# NG2094_Connector_B.net
KiCad netlist of a schematic drawn in Altium Designer
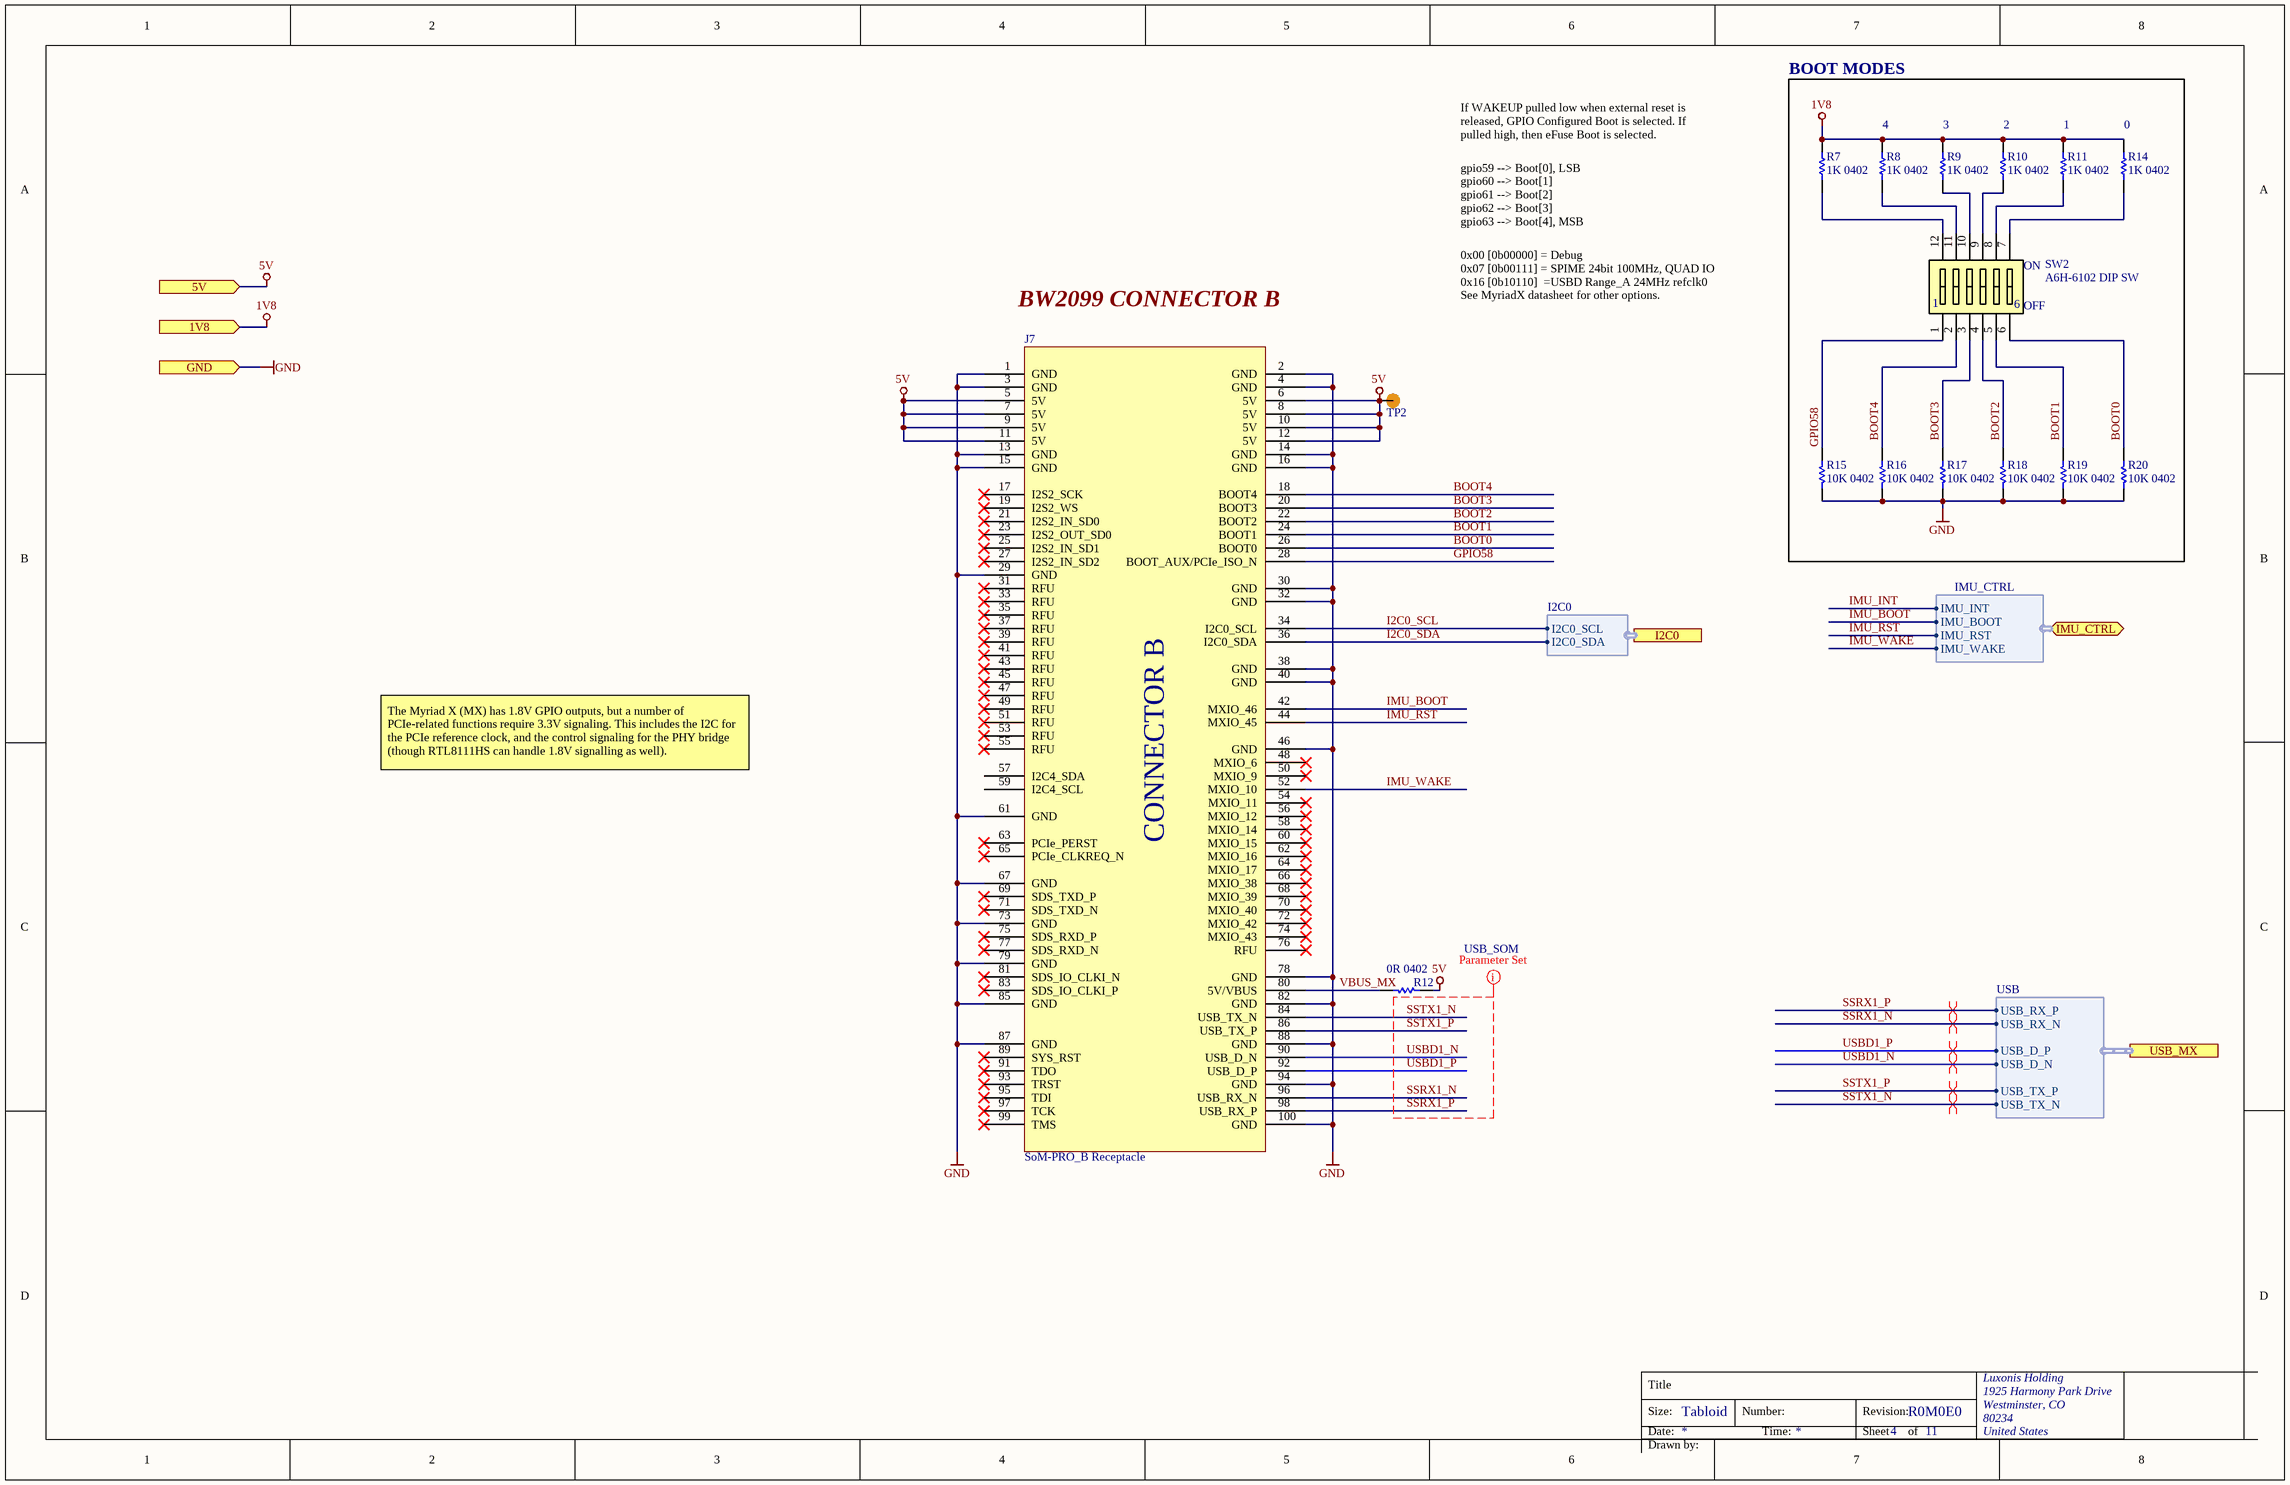
[diagram p0: NG2094_Connector_B.SchDoc]

(export (version "E")
  (design (tool "Eeschema 10.0.6"))
  (components
    (comp (ref "J7")
      (value "SoM-PRO_B Receptacle")
      (footprint "BW2099_SoM:CON_B_BW2099_SoM_DF40HC-3.0-100DS-0.4V_minpad")
      (description "CONN RCPT 100POS 0.4MM SMD GOLD")
      (libsource (lib "BW2099_SoM") (part "DF40HC(3.0)-100DS-0.4V_SoM-PRO_B"))
    )
    (comp (ref "R7")
      (value "1K 0402")
      (footprint "RES_Altium_Vault_Generic:RESC0402(1005)_L")
      (fields (field (name "TOLERANCE") "1%"))
      (libsource (lib "LuxonisMaster") (part "RC0402FR-071KL"))
    )
    (comp (ref "R8")
      (value "1K 0402")
      (footprint "RES_Altium_Vault_Generic:RESC0402(1005)_L")
      (fields (field (name "TOLERANCE") "1%"))
      (libsource (lib "LuxonisMaster") (part "RC0402FR-071KL"))
    )
    (comp (ref "R9")
      (value "1K 0402")
      (footprint "RES_Altium_Vault_Generic:RESC0402(1005)_L")
      (fields (field (name "TOLERANCE") "1%"))
      (libsource (lib "LuxonisMaster") (part "RC0402FR-071KL"))
    )
    (comp (ref "R10")
      (value "1K 0402")
      (footprint "RES_Altium_Vault_Generic:RESC0402(1005)_L")
      (fields (field (name "TOLERANCE") "1%"))
      (libsource (lib "LuxonisMaster") (part "RC0402FR-071KL"))
    )
    (comp (ref "R11")
      (value "1K 0402")
      (footprint "RES_Altium_Vault_Generic:RESC0402(1005)_L")
      (fields (field (name "TOLERANCE") "1%"))
      (libsource (lib "LuxonisMaster") (part "RC0402FR-071KL"))
    )
    (comp (ref "R12")
      (value "0R 0402")
      (footprint "RES_Altium_Vault_Generic:RESC0402(1005)_L")
      (description "RES SMD 0 OHM JUMPER 1/16W 0402")
      (fields (field (name "TOLERANCE") "5%"))
      (libsource (lib "LuxonisMaster") (part "CRCW04020000Z0ED"))
    )
    (comp (ref "R14")
      (value "1K 0402")
      (footprint "RES_Altium_Vault_Generic:RESC0402(1005)_L")
      (fields (field (name "TOLERANCE") "1%"))
      (libsource (lib "LuxonisMaster") (part "RC0402FR-071KL"))
    )
    (comp (ref "R15")
      (value "10K 0402")
      (footprint "RES_Altium_Vault_Generic:RESC0402(1005)_L")
      (fields (field (name "TOLERANCE") "1%"))
      (libsource (lib "LuxonisMaster") (part "RC0402FR-1310KL"))
    )
    (comp (ref "R16")
      (value "10K 0402")
      (footprint "RES_Altium_Vault_Generic:RESC0402(1005)_L")
      (fields (field (name "TOLERANCE") "1%"))
      (libsource (lib "LuxonisMaster") (part "RC0402FR-1310KL"))
    )
    (comp (ref "R17")
      (value "10K 0402")
      (footprint "RES_Altium_Vault_Generic:RESC0402(1005)_L")
      (fields (field (name "TOLERANCE") "1%"))
      (libsource (lib "LuxonisMaster") (part "RC0402FR-1310KL"))
    )
    (comp (ref "R18")
      (value "10K 0402")
      (footprint "RES_Altium_Vault_Generic:RESC0402(1005)_L")
      (fields (field (name "TOLERANCE") "1%"))
      (libsource (lib "LuxonisMaster") (part "RC0402FR-1310KL"))
    )
    (comp (ref "R19")
      (value "10K 0402")
      (footprint "RES_Altium_Vault_Generic:RESC0402(1005)_L")
      (fields (field (name "TOLERANCE") "1%"))
      (libsource (lib "LuxonisMaster") (part "RC0402FR-1310KL"))
    )
    (comp (ref "R20")
      (value "10K 0402")
      (footprint "RES_Altium_Vault_Generic:RESC0402(1005)_L")
      (fields (field (name "TOLERANCE") "1%"))
      (libsource (lib "LuxonisMaster") (part "RC0402FR-1310KL"))
    )
    (comp (ref "SW2")
      (value "A6H-6102 DIP SW")
      (footprint "LuxonisMaster:A6H-610x")
      (description "SWITCH SLIDE DIP SPST 25MA 24V (SEALED)")
      (libsource (lib "LuxonisMaster") (part "A6H-6102"))
    )
    (comp (ref "TP2")
      (value "TP100_200_NS")
      (footprint "LuxonisMaster:TP100_200_NS")
      (libsource (lib "LuxonisMaster") (part "TEST_POINT"))
    )
  )
  (nets
    (net (code "4") (name "/BOOT0") (class "Default")
      (node (ref "J7") (pin "26") (pinfunction "BOOT0_26") (pintype "passive"))
      (node (ref "R20") (pin "1") (pinfunction "1_1") (pintype "passive"))
      (node (ref "SW2") (pin "6") (pinfunction "6_6") (pintype "passive"))
    )
    (net (code "5") (name "/BOOT1") (class "Default")
      (node (ref "J7") (pin "24") (pinfunction "BOOT1_24") (pintype "passive"))
      (node (ref "R19") (pin "1") (pinfunction "1_1") (pintype "passive"))
      (node (ref "SW2") (pin "5") (pinfunction "5_5") (pintype "passive"))
    )
    (net (code "6") (name "/BOOT2") (class "Default")
      (node (ref "J7") (pin "22") (pinfunction "BOOT2_22") (pintype "passive"))
      (node (ref "R18") (pin "1") (pinfunction "1_1") (pintype "passive"))
      (node (ref "SW2") (pin "4") (pinfunction "4_4") (pintype "passive"))
    )
    (net (code "7") (name "/BOOT3") (class "Default")
      (node (ref "J7") (pin "20") (pinfunction "BOOT3_20") (pintype "passive"))
      (node (ref "R17") (pin "1") (pinfunction "1_1") (pintype "passive"))
      (node (ref "SW2") (pin "3") (pinfunction "3_3") (pintype "passive"))
    )
    (net (code "8") (name "/BOOT4") (class "Default")
      (node (ref "J7") (pin "18") (pinfunction "BOOT4_18") (pintype "passive"))
      (node (ref "R16") (pin "1") (pinfunction "1_1") (pintype "passive"))
      (node (ref "SW2") (pin "2") (pinfunction "2_2") (pintype "passive"))
    )
    (net (code "9") (name "/GPIO58") (class "Default")
      (node (ref "J7") (pin "28") (pinfunction "BOOT_AUX/PCIe_ISO_N_28") (pintype "passive"))
      (node (ref "R15") (pin "1") (pinfunction "1_1") (pintype "passive"))
      (node (ref "SW2") (pin "1") (pinfunction "1_1") (pintype "passive"))
    )
    (net (code "10") (name "/I2C0_SCL") (class "Default")
      (node (ref "J7") (pin "34") (pinfunction "I2C0_SCL_34") (pintype "passive"))
    )
    (net (code "11") (name "/I2C0_SDA") (class "Default")
      (node (ref "J7") (pin "36") (pinfunction "I2C0_SDA_36") (pintype "passive"))
    )
    (net (code "12") (name "/IMU_BOOT") (class "Default")
      (node (ref "J7") (pin "42") (pinfunction "MXIO_46_42") (pintype "passive"))
    )
    (net (code "14") (name "/IMU_RST") (class "Default")
      (node (ref "J7") (pin "44") (pinfunction "MXIO_45_44") (pintype "passive"))
    )
    (net (code "15") (name "/IMU_WAKE") (class "Default")
      (node (ref "J7") (pin "52") (pinfunction "MXIO_10_52") (pintype "passive"))
    )
    (net (code "16") (name "/SSRX1_N") (class "Default")
      (node (ref "J7") (pin "96") (pinfunction "USB_RX_N_96") (pintype "passive"))
    )
    (net (code "17") (name "/SSRX1_P") (class "Default")
      (node (ref "J7") (pin "98") (pinfunction "USB_RX_P_98") (pintype "passive"))
    )
    (net (code "18") (name "/SSTX1_N") (class "Default")
      (node (ref "J7") (pin "84") (pinfunction "USB_TX_N_84") (pintype "passive"))
    )
    (net (code "19") (name "/SSTX1_P") (class "Default")
      (node (ref "J7") (pin "86") (pinfunction "USB_TX_P_86") (pintype "passive"))
    )
    (net (code "20") (name "/USBD1_N") (class "Default")
      (node (ref "J7") (pin "90") (pinfunction "USB_D_N_90") (pintype "passive"))
    )
    (net (code "21") (name "/USBD1_P") (class "Default")
      (node (ref "J7") (pin "92") (pinfunction "USB_D_P_92") (pintype "passive"))
    )
    (net (code "22") (name "/VBUS_MX") (class "Default")
      (node (ref "J7") (pin "80") (pinfunction "5V/VBUS_80") (pintype "passive"))
      (node (ref "R12") (pin "1") (pinfunction "1_1") (pintype "passive"))
    )
    (net (code "26") (name "1V8") (class "Default")
      (node (ref "R10") (pin "2") (pinfunction "2_2") (pintype "passive"))
      (node (ref "R11") (pin "2") (pinfunction "2_2") (pintype "passive"))
      (node (ref "R14") (pin "2") (pinfunction "2_2") (pintype "passive"))
      (node (ref "R7") (pin "2") (pinfunction "2_2") (pintype "passive"))
      (node (ref "R8") (pin "2") (pinfunction "2_2") (pintype "passive"))
      (node (ref "R9") (pin "2") (pinfunction "2_2") (pintype "passive"))
    )
    (net (code "27") (name "5V") (class "Default")
      (node (ref "J7") (pin "10") (pinfunction "5V_10") (pintype "passive"))
      (node (ref "J7") (pin "11") (pinfunction "5V_11") (pintype "passive"))
      (node (ref "J7") (pin "12") (pinfunction "5V_12") (pintype "passive"))
      (node (ref "J7") (pin "5") (pinfunction "5V_5") (pintype "passive"))
      (node (ref "J7") (pin "6") (pinfunction "5V_6") (pintype "passive"))
      (node (ref "J7") (pin "7") (pinfunction "5V_7") (pintype "passive"))
      (node (ref "J7") (pin "8") (pinfunction "5V_8") (pintype "passive"))
      (node (ref "J7") (pin "9") (pinfunction "5V_9") (pintype "passive"))
      (node (ref "R12") (pin "2") (pinfunction "2_2") (pintype "passive"))
      (node (ref "TP2") (pin "1") (pintype "passive"))
    )
    (net (code "28") (name "GND") (class "Default")
      (node (ref "J7") (pin "1") (pinfunction "GND_1") (pintype "passive"))
      (node (ref "J7") (pin "100") (pinfunction "GND_100") (pintype "passive"))
      (node (ref "J7") (pin "13") (pinfunction "GND_13") (pintype "passive"))
      (node (ref "J7") (pin "14") (pinfunction "GND_14") (pintype "passive"))
      (node (ref "J7") (pin "15") (pinfunction "GND_15") (pintype "passive"))
      (node (ref "J7") (pin "16") (pinfunction "GND_16") (pintype "passive"))
      (node (ref "J7") (pin "2") (pinfunction "GND_2") (pintype "passive"))
      (node (ref "J7") (pin "29") (pinfunction "GND_29") (pintype "passive"))
      (node (ref "J7") (pin "3") (pinfunction "GND_3") (pintype "passive"))
      (node (ref "J7") (pin "30") (pinfunction "GND_30") (pintype "passive"))
      (node (ref "J7") (pin "32") (pinfunction "GND_32") (pintype "passive"))
      (node (ref "J7") (pin "38") (pinfunction "GND_38") (pintype "passive"))
      (node (ref "J7") (pin "4") (pinfunction "GND_4") (pintype "passive"))
      (node (ref "J7") (pin "40") (pinfunction "GND_40") (pintype "passive"))
      (node (ref "J7") (pin "46") (pinfunction "GND_46") (pintype "passive"))
      (node (ref "J7") (pin "61") (pinfunction "GND_61") (pintype "passive"))
      (node (ref "J7") (pin "67") (pinfunction "GND_67") (pintype "passive"))
      (node (ref "J7") (pin "73") (pinfunction "GND_73") (pintype "passive"))
      (node (ref "J7") (pin "78") (pinfunction "GND_78") (pintype "passive"))
      (node (ref "J7") (pin "79") (pinfunction "GND_79") (pintype "passive"))
      (node (ref "J7") (pin "82") (pinfunction "GND_82") (pintype "passive"))
      (node (ref "J7") (pin "85") (pinfunction "GND_85") (pintype "passive"))
      (node (ref "J7") (pin "87") (pinfunction "GND_87") (pintype "passive"))
      (node (ref "J7") (pin "88") (pinfunction "GND_88") (pintype "passive"))
      (node (ref "J7") (pin "94") (pinfunction "GND_94") (pintype "passive"))
      (node (ref "R15") (pin "2") (pinfunction "2_2") (pintype "passive"))
      (node (ref "R16") (pin "2") (pinfunction "2_2") (pintype "passive"))
      (node (ref "R17") (pin "2") (pinfunction "2_2") (pintype "passive"))
      (node (ref "R18") (pin "2") (pinfunction "2_2") (pintype "passive"))
      (node (ref "R19") (pin "2") (pinfunction "2_2") (pintype "passive"))
      (node (ref "R20") (pin "2") (pinfunction "2_2") (pintype "passive"))
    )
    (net (code "29") (name "Net-(R7-Pad1)") (class "Default")
      (node (ref "R7") (pin "1") (pinfunction "1_1") (pintype "passive"))
      (node (ref "SW2") (pin "12") (pinfunction "12_12") (pintype "passive"))
    )
    (net (code "30") (name "Net-(R8-Pad1)") (class "Default")
      (node (ref "R8") (pin "1") (pinfunction "1_1") (pintype "passive"))
      (node (ref "SW2") (pin "11") (pinfunction "11_11") (pintype "passive"))
    )
    (net (code "31") (name "Net-(R9-Pad1)") (class "Default")
      (node (ref "R9") (pin "1") (pinfunction "1_1") (pintype "passive"))
      (node (ref "SW2") (pin "10") (pinfunction "10_10") (pintype "passive"))
    )
    (net (code "32") (name "Net-(R10-Pad1)") (class "Default")
      (node (ref "R10") (pin "1") (pinfunction "1_1") (pintype "passive"))
      (node (ref "SW2") (pin "9") (pinfunction "9_9") (pintype "passive"))
    )
    (net (code "33") (name "Net-(R11-Pad1)") (class "Default")
      (node (ref "R11") (pin "1") (pinfunction "1_1") (pintype "passive"))
      (node (ref "SW2") (pin "8") (pinfunction "8_8") (pintype "passive"))
    )
    (net (code "34") (name "Net-(R14-Pad1)") (class "Default")
      (node (ref "R14") (pin "1") (pinfunction "1_1") (pintype "passive"))
      (node (ref "SW2") (pin "7") (pinfunction "7_7") (pintype "passive"))
    )
    (net (code "35") (name "unconnected-(J7-I2C4_SCL-Pad59)") (class "Default")
      (node (ref "J7") (pin "59") (pinfunction "I2C4_SCL_59") (pintype "passive"))
    )
    (net (code "36") (name "unconnected-(J7-I2C4_SDA-Pad57)") (class "Default")
      (node (ref "J7") (pin "57") (pinfunction "I2C4_SDA_57") (pintype "passive"))
    )
    (net (code "37") (name "unconnected-(J7-I2S2_IN_SD0-Pad21)") (class "Default")
      (node (ref "J7") (pin "21") (pinfunction "I2S2_IN_SD0_21") (pintype "passive+no_connect"))
    )
    (net (code "38") (name "unconnected-(J7-I2S2_IN_SD1-Pad25)") (class "Default")
      (node (ref "J7") (pin "25") (pinfunction "I2S2_IN_SD1_25") (pintype "passive+no_connect"))
    )
    (net (code "39") (name "unconnected-(J7-I2S2_IN_SD2-Pad27)") (class "Default")
      (node (ref "J7") (pin "27") (pinfunction "I2S2_IN_SD2_27") (pintype "passive+no_connect"))
    )
    (net (code "40") (name "unconnected-(J7-I2S2_OUT_SD0-Pad23)") (class "Default")
      (node (ref "J7") (pin "23") (pinfunction "I2S2_OUT_SD0_23") (pintype "passive+no_connect"))
    )
    (net (code "41") (name "unconnected-(J7-I2S2_SCK-Pad17)") (class "Default")
      (node (ref "J7") (pin "17") (pinfunction "I2S2_SCK_17") (pintype "passive+no_connect"))
    )
    (net (code "42") (name "unconnected-(J7-I2S2_WS-Pad19)") (class "Default")
      (node (ref "J7") (pin "19") (pinfunction "I2S2_WS_19") (pintype "passive+no_connect"))
    )
    (net (code "43") (name "unconnected-(J7-MXIO_6-Pad48)") (class "Default")
      (node (ref "J7") (pin "48") (pinfunction "MXIO_6_48") (pintype "passive+no_connect"))
    )
    (net (code "44") (name "unconnected-(J7-MXIO_9-Pad50)") (class "Default")
      (node (ref "J7") (pin "50") (pinfunction "MXIO_9_50") (pintype "passive+no_connect"))
    )
    (net (code "45") (name "unconnected-(J7-MXIO_11-Pad54)") (class "Default")
      (node (ref "J7") (pin "54") (pinfunction "MXIO_11_54") (pintype "passive+no_connect"))
    )
    (net (code "46") (name "unconnected-(J7-MXIO_12-Pad56)") (class "Default")
      (node (ref "J7") (pin "56") (pinfunction "MXIO_12_56") (pintype "passive+no_connect"))
    )
    (net (code "47") (name "unconnected-(J7-MXIO_14-Pad58)") (class "Default")
      (node (ref "J7") (pin "58") (pinfunction "MXIO_14_58") (pintype "passive+no_connect"))
    )
    (net (code "48") (name "unconnected-(J7-MXIO_15-Pad60)") (class "Default")
      (node (ref "J7") (pin "60") (pinfunction "MXIO_15_60") (pintype "passive+no_connect"))
    )
    (net (code "49") (name "unconnected-(J7-MXIO_16-Pad62)") (class "Default")
      (node (ref "J7") (pin "62") (pinfunction "MXIO_16_62") (pintype "passive+no_connect"))
    )
    (net (code "50") (name "unconnected-(J7-MXIO_17-Pad64)") (class "Default")
      (node (ref "J7") (pin "64") (pinfunction "MXIO_17_64") (pintype "passive+no_connect"))
    )
    (net (code "51") (name "unconnected-(J7-MXIO_38-Pad66)") (class "Default")
      (node (ref "J7") (pin "66") (pinfunction "MXIO_38_66") (pintype "passive+no_connect"))
    )
    (net (code "52") (name "unconnected-(J7-MXIO_39-Pad68)") (class "Default")
      (node (ref "J7") (pin "68") (pinfunction "MXIO_39_68") (pintype "passive+no_connect"))
    )
    (net (code "53") (name "unconnected-(J7-MXIO_40-Pad70)") (class "Default")
      (node (ref "J7") (pin "70") (pinfunction "MXIO_40_70") (pintype "passive+no_connect"))
    )
    (net (code "54") (name "unconnected-(J7-MXIO_42-Pad72)") (class "Default")
      (node (ref "J7") (pin "72") (pinfunction "MXIO_42_72") (pintype "passive+no_connect"))
    )
    (net (code "55") (name "unconnected-(J7-MXIO_43-Pad74)") (class "Default")
      (node (ref "J7") (pin "74") (pinfunction "MXIO_43_74") (pintype "passive+no_connect"))
    )
    (net (code "56") (name "unconnected-(J7-PCIe_CLKREQ_N-Pad65)") (class "Default")
      (node (ref "J7") (pin "65") (pinfunction "PCIe_CLKREQ_N_65") (pintype "passive+no_connect"))
    )
    (net (code "57") (name "unconnected-(J7-PCIe_PERST-Pad63)") (class "Default")
      (node (ref "J7") (pin "63") (pinfunction "PCIe_PERST_63") (pintype "passive+no_connect"))
    )
    (net (code "58") (name "unconnected-(J7-RFU-Pad31)") (class "Default")
      (node (ref "J7") (pin "31") (pinfunction "RFU_31") (pintype "passive+no_connect"))
    )
    (net (code "59") (name "unconnected-(J7-RFU-Pad33)") (class "Default")
      (node (ref "J7") (pin "33") (pinfunction "RFU_33") (pintype "passive+no_connect"))
    )
    (net (code "60") (name "unconnected-(J7-RFU-Pad35)") (class "Default")
      (node (ref "J7") (pin "35") (pinfunction "RFU_35") (pintype "passive+no_connect"))
    )
    (net (code "61") (name "unconnected-(J7-RFU-Pad37)") (class "Default")
      (node (ref "J7") (pin "37") (pinfunction "RFU_37") (pintype "passive+no_connect"))
    )
    (net (code "62") (name "unconnected-(J7-RFU-Pad39)") (class "Default")
      (node (ref "J7") (pin "39") (pinfunction "RFU_39") (pintype "passive+no_connect"))
    )
    (net (code "63") (name "unconnected-(J7-RFU-Pad41)") (class "Default")
      (node (ref "J7") (pin "41") (pinfunction "RFU_41") (pintype "passive+no_connect"))
    )
    (net (code "64") (name "unconnected-(J7-RFU-Pad43)") (class "Default")
      (node (ref "J7") (pin "43") (pinfunction "RFU_43") (pintype "passive+no_connect"))
    )
    (net (code "65") (name "unconnected-(J7-RFU-Pad45)") (class "Default")
      (node (ref "J7") (pin "45") (pinfunction "RFU_45") (pintype "passive+no_connect"))
    )
    (net (code "66") (name "unconnected-(J7-RFU-Pad47)") (class "Default")
      (node (ref "J7") (pin "47") (pinfunction "RFU_47") (pintype "passive+no_connect"))
    )
    (net (code "67") (name "unconnected-(J7-RFU-Pad49)") (class "Default")
      (node (ref "J7") (pin "49") (pinfunction "RFU_49") (pintype "passive+no_connect"))
    )
    (net (code "68") (name "unconnected-(J7-RFU-Pad51)") (class "Default")
      (node (ref "J7") (pin "51") (pinfunction "RFU_51") (pintype "passive+no_connect"))
    )
    (net (code "69") (name "unconnected-(J7-RFU-Pad53)") (class "Default")
      (node (ref "J7") (pin "53") (pinfunction "RFU_53") (pintype "passive+no_connect"))
    )
    (net (code "70") (name "unconnected-(J7-RFU-Pad55)") (class "Default")
      (node (ref "J7") (pin "55") (pinfunction "RFU_55") (pintype "passive+no_connect"))
    )
    (net (code "71") (name "unconnected-(J7-RFU-Pad76)") (class "Default")
      (node (ref "J7") (pin "76") (pinfunction "RFU_76") (pintype "passive+no_connect"))
    )
    (net (code "72") (name "unconnected-(J7-SDS_IO_CLKI_N-Pad81)") (class "Default")
      (node (ref "J7") (pin "81") (pinfunction "SDS_IO_CLKI_N_81") (pintype "passive+no_connect"))
    )
    (net (code "73") (name "unconnected-(J7-SDS_IO_CLKI_P-Pad83)") (class "Default")
      (node (ref "J7") (pin "83") (pinfunction "SDS_IO_CLKI_P_83") (pintype "passive+no_connect"))
    )
    (net (code "74") (name "unconnected-(J7-SDS_RXD_N-Pad77)") (class "Default")
      (node (ref "J7") (pin "77") (pinfunction "SDS_RXD_N_77") (pintype "passive+no_connect"))
    )
    (net (code "75") (name "unconnected-(J7-SDS_RXD_P-Pad75)") (class "Default")
      (node (ref "J7") (pin "75") (pinfunction "SDS_RXD_P_75") (pintype "passive+no_connect"))
    )
    (net (code "76") (name "unconnected-(J7-SDS_TXD_N-Pad71)") (class "Default")
      (node (ref "J7") (pin "71") (pinfunction "SDS_TXD_N_71") (pintype "passive+no_connect"))
    )
    (net (code "77") (name "unconnected-(J7-SDS_TXD_P-Pad69)") (class "Default")
      (node (ref "J7") (pin "69") (pinfunction "SDS_TXD_P_69") (pintype "passive+no_connect"))
    )
    (net (code "78") (name "unconnected-(J7-SYS_RST-Pad89)") (class "Default")
      (node (ref "J7") (pin "89") (pinfunction "SYS_RST_89") (pintype "passive+no_connect"))
    )
    (net (code "79") (name "unconnected-(J7-TCK-Pad97)") (class "Default")
      (node (ref "J7") (pin "97") (pinfunction "TCK_97") (pintype "passive+no_connect"))
    )
    (net (code "80") (name "unconnected-(J7-TDI-Pad95)") (class "Default")
      (node (ref "J7") (pin "95") (pinfunction "TDI_95") (pintype "passive+no_connect"))
    )
    (net (code "81") (name "unconnected-(J7-TDO-Pad91)") (class "Default")
      (node (ref "J7") (pin "91") (pinfunction "TDO_91") (pintype "passive+no_connect"))
    )
    (net (code "82") (name "unconnected-(J7-TMS-Pad99)") (class "Default")
      (node (ref "J7") (pin "99") (pinfunction "TMS_99") (pintype "passive+no_connect"))
    )
    (net (code "83") (name "unconnected-(J7-TRST-Pad93)") (class "Default")
      (node (ref "J7") (pin "93") (pinfunction "TRST_93") (pintype "passive+no_connect"))
    )
  )
)
